# monster_dac.net
KiCad netlist of a schematic drawn in EAGLE
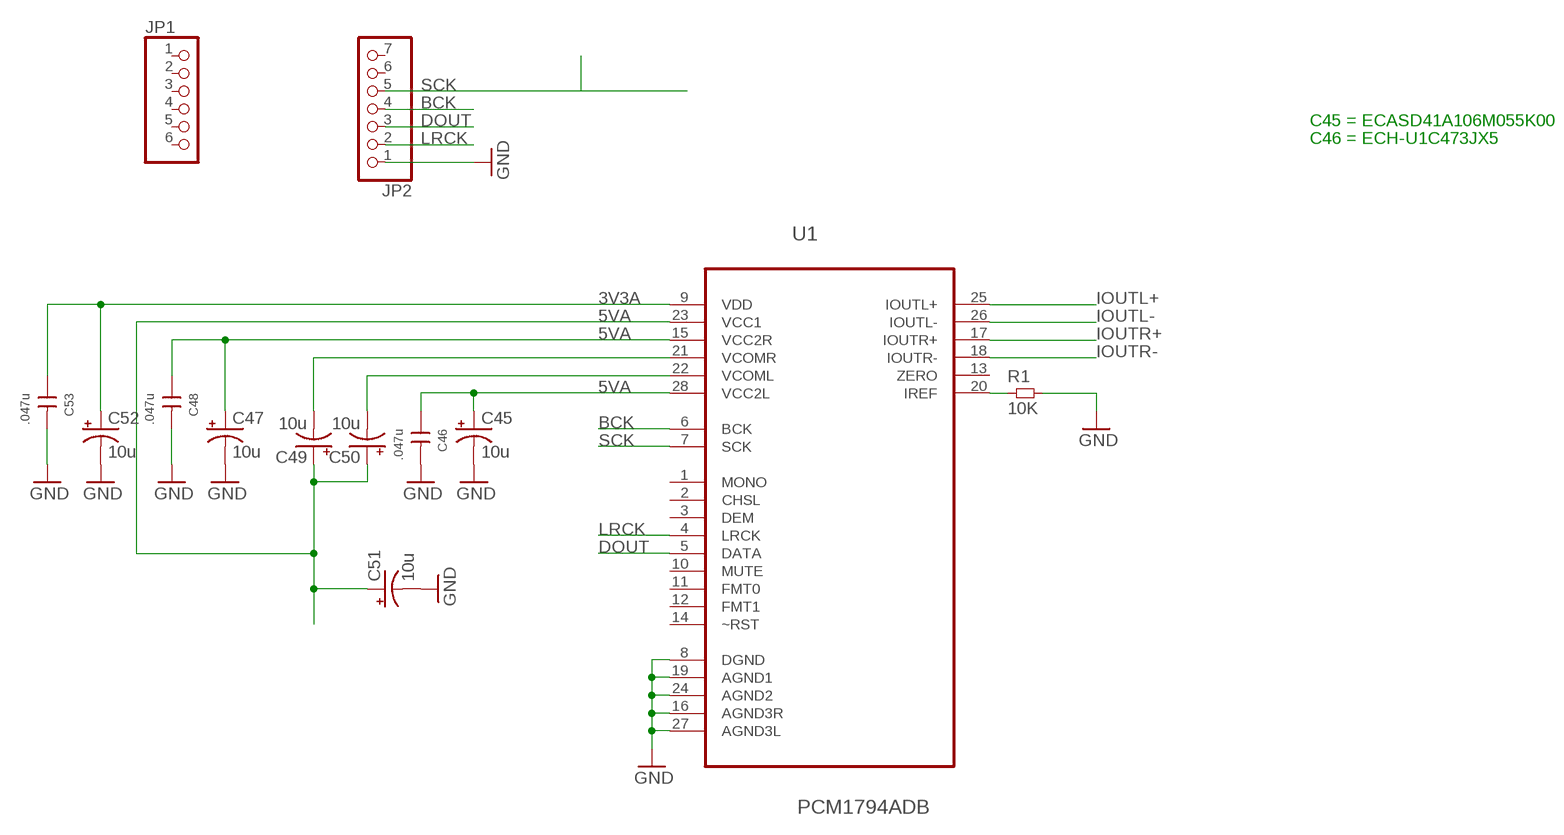
[diagram p0: schematic, sheet 1]
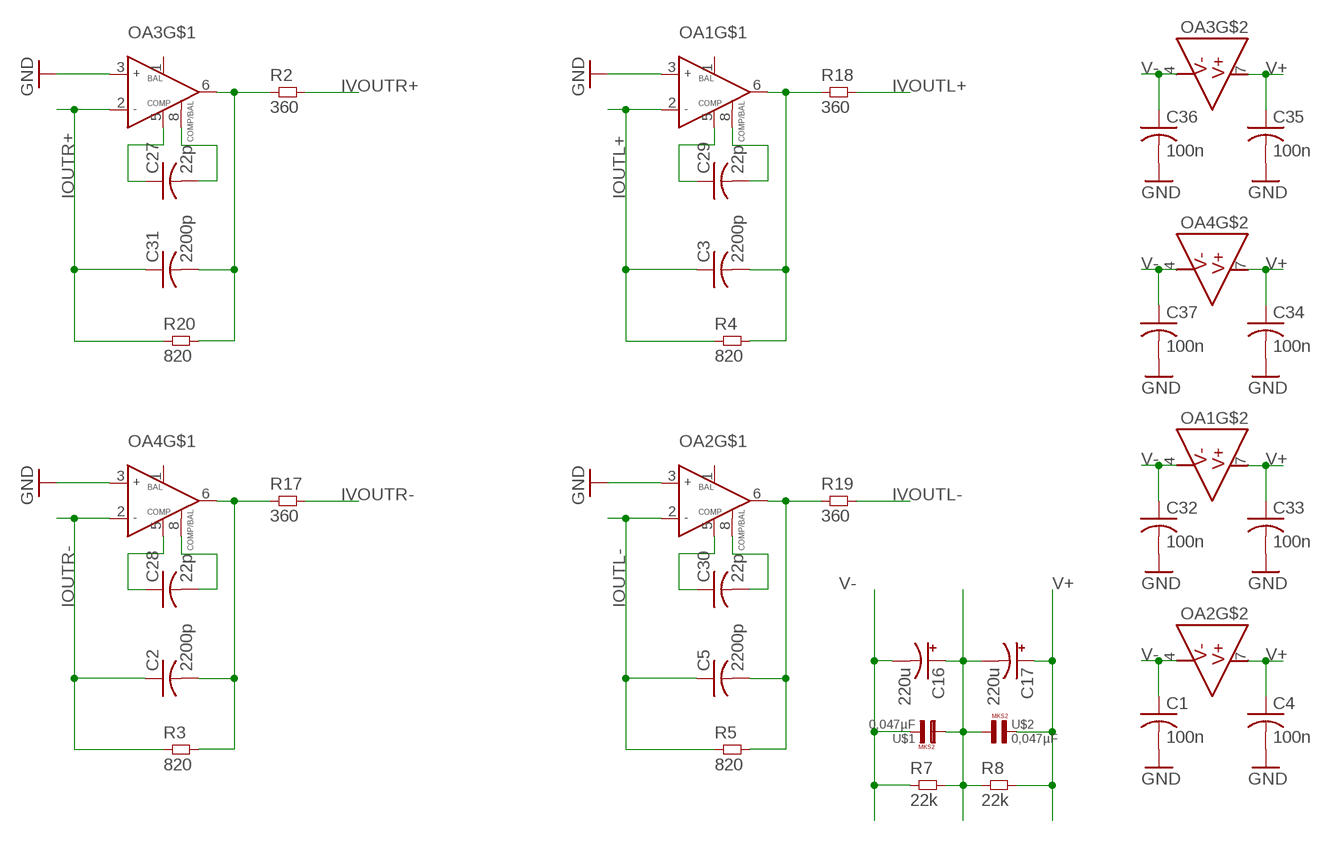
[diagram p1: schematic, sheet 2]
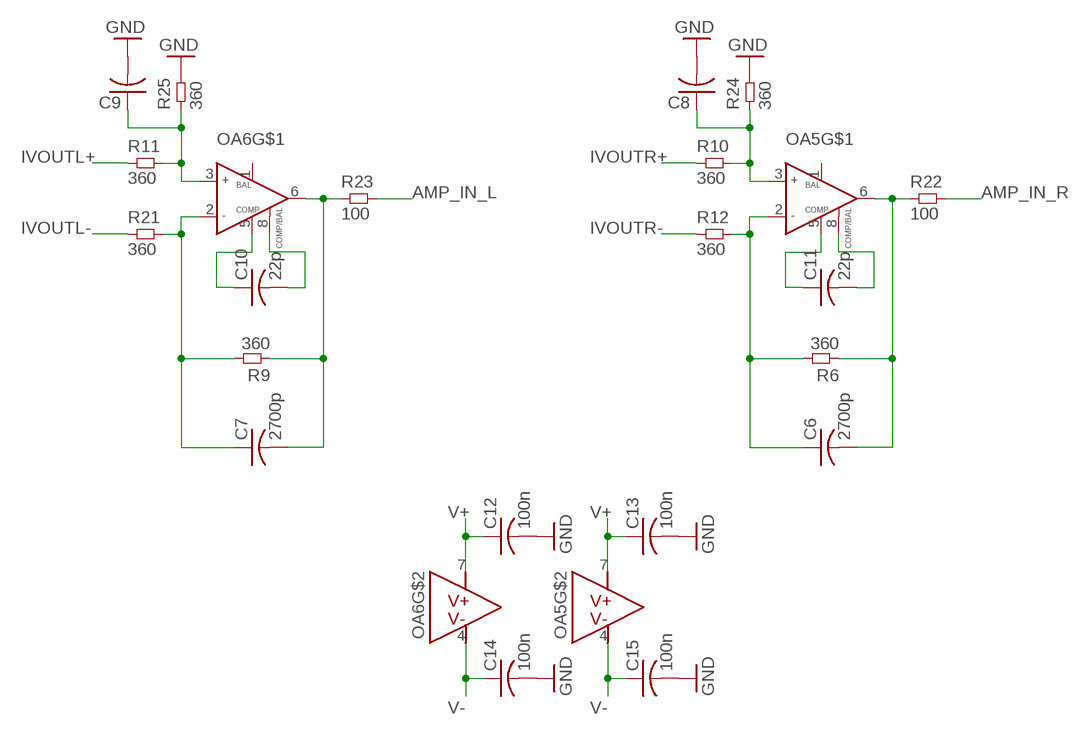
[diagram p2: schematic, sheet 3]

(export (version "E")
  (design (tool "Eeschema 10.0.6"))
  (components
    (comp (ref "C1")
      (value "100n")
      (footprint "eagle-import:C0603")
      (libsource (lib "eagle-import") (part "C-USC0603"))
    )
    (comp (ref "C2")
      (value "2200p")
      (footprint "eagle-import:C0603")
      (libsource (lib "eagle-import") (part "C-USC0603"))
    )
    (comp (ref "C3")
      (value "2200p")
      (footprint "eagle-import:C0603")
      (libsource (lib "eagle-import") (part "C-USC0603"))
    )
    (comp (ref "C4")
      (value "100n")
      (footprint "eagle-import:C0603")
      (libsource (lib "eagle-import") (part "C-USC0603"))
    )
    (comp (ref "C5")
      (value "2200p")
      (footprint "eagle-import:C0603")
      (libsource (lib "eagle-import") (part "C-USC0603"))
    )
    (comp (ref "C16")
      (value "220u")
      (footprint "eagle-import:E2,5-6")
      (libsource (lib "eagle-import") (part "CPOL-USE2.5-6"))
    )
    (comp (ref "C17")
      (value "220u")
      (footprint "eagle-import:E2,5-6")
      (libsource (lib "eagle-import") (part "CPOL-USE2.5-6"))
    )
    (comp (ref "C27")
      (value "22p")
      (footprint "eagle-import:C0603")
      (libsource (lib "eagle-import") (part "C-USC0603"))
    )
    (comp (ref "C28")
      (value "22p")
      (footprint "eagle-import:C0603")
      (libsource (lib "eagle-import") (part "C-USC0603"))
    )
    (comp (ref "C29")
      (value "22p")
      (footprint "eagle-import:C0603")
      (libsource (lib "eagle-import") (part "C-USC0603"))
    )
    (comp (ref "C30")
      (value "22p")
      (footprint "eagle-import:C0603")
      (libsource (lib "eagle-import") (part "C-USC0603"))
    )
    (comp (ref "C31")
      (value "2200p")
      (footprint "eagle-import:C0603")
      (libsource (lib "eagle-import") (part "C-USC0603"))
    )
    (comp (ref "C32")
      (value "100n")
      (footprint "eagle-import:C0603")
      (libsource (lib "eagle-import") (part "C-USC0603"))
    )
    (comp (ref "C33")
      (value "100n")
      (footprint "eagle-import:C0603")
      (libsource (lib "eagle-import") (part "C-USC0603"))
    )
    (comp (ref "C34")
      (value "100n")
      (footprint "eagle-import:C0603")
      (libsource (lib "eagle-import") (part "C-USC0603"))
    )
    (comp (ref "C35")
      (value "100n")
      (footprint "eagle-import:C0603")
      (libsource (lib "eagle-import") (part "C-USC0603"))
    )
    (comp (ref "C36")
      (value "100n")
      (footprint "eagle-import:C0603")
      (libsource (lib "eagle-import") (part "C-USC0603"))
    )
    (comp (ref "C37")
      (value "100n")
      (footprint "eagle-import:C0603")
      (libsource (lib "eagle-import") (part "C-USC0603"))
    )
    (comp (ref "OA1")
      (value "NE5534ADSOIC8")
      (footprint "eagle-import:SOIC-8")
      (libsource (lib "eagle-import") (part "NE5534SOIC8AD"))
    )
    (comp (ref "OA2")
      (value "NE5534ADSOIC8")
      (footprint "eagle-import:SOIC-8")
      (libsource (lib "eagle-import") (part "NE5534SOIC8AD"))
    )
    (comp (ref "OA3")
      (value "NE5534ADSOIC8")
      (footprint "eagle-import:SOIC-8")
      (libsource (lib "eagle-import") (part "NE5534SOIC8AD"))
    )
    (comp (ref "OA4")
      (value "NE5534ADSOIC8")
      (footprint "eagle-import:SOIC-8")
      (libsource (lib "eagle-import") (part "NE5534SOIC8AD"))
    )
    (comp (ref "R2")
      (value "360")
      (footprint "eagle-import:0603L3")
      (libsource (lib "eagle-import") (part "RES0603L3"))
    )
    (comp (ref "R3")
      (value "820")
      (footprint "eagle-import:0603L3")
      (libsource (lib "eagle-import") (part "RES0603L3"))
    )
    (comp (ref "R4")
      (value "820")
      (footprint "eagle-import:0603L3")
      (libsource (lib "eagle-import") (part "RES0603L3"))
    )
    (comp (ref "R5")
      (value "820")
      (footprint "eagle-import:0603L3")
      (libsource (lib "eagle-import") (part "RES0603L3"))
    )
    (comp (ref "R7")
      (value "22k")
      (footprint "eagle-import:0603L3")
      (libsource (lib "eagle-import") (part "RES0603L3"))
    )
    (comp (ref "R8")
      (value "22k")
      (footprint "eagle-import:0603L3")
      (libsource (lib "eagle-import") (part "RES0603L3"))
    )
    (comp (ref "R17")
      (value "360")
      (footprint "eagle-import:0603L3")
      (libsource (lib "eagle-import") (part "RES0603L3"))
    )
    (comp (ref "R18")
      (value "360")
      (footprint "eagle-import:0603L3")
      (libsource (lib "eagle-import") (part "RES0603L3"))
    )
    (comp (ref "R19")
      (value "360")
      (footprint "eagle-import:0603L3")
      (libsource (lib "eagle-import") (part "RES0603L3"))
    )
    (comp (ref "R20")
      (value "820")
      (footprint "eagle-import:0603L3")
      (libsource (lib "eagle-import") (part "RES0603L3"))
    )
    (comp (ref "U$1")
      (value "0,047µF")
      (footprint "eagle-import:R5B2K5")
      (libsource (lib "eagle-import") (part "0,047µF"))
    )
    (comp (ref "U$2")
      (value "0,047µF")
      (footprint "eagle-import:R5B2K5")
      (libsource (lib "eagle-import") (part "0,047µF"))
    )
    (comp (ref "C6")
      (value "2700p")
      (footprint "eagle-import:C0603")
      (libsource (lib "eagle-import") (part "C-USC0603"))
    )
    (comp (ref "C7")
      (value "2700p")
      (footprint "eagle-import:C0603")
      (libsource (lib "eagle-import") (part "C-USC0603"))
    )
    (comp (ref "C8")
      (value "C-USC0603")
      (footprint "eagle-import:C0603")
      (libsource (lib "eagle-import") (part "C-USC0603"))
    )
    (comp (ref "C9")
      (value "C-USC0603")
      (footprint "eagle-import:C0603")
      (libsource (lib "eagle-import") (part "C-USC0603"))
    )
    (comp (ref "C10")
      (value "22p")
      (footprint "eagle-import:C0603")
      (libsource (lib "eagle-import") (part "C-USC0603"))
    )
    (comp (ref "C11")
      (value "22p")
      (footprint "eagle-import:C0603")
      (libsource (lib "eagle-import") (part "C-USC0603"))
    )
    (comp (ref "C12")
      (value "100n")
      (footprint "eagle-import:C0603")
      (libsource (lib "eagle-import") (part "C-USC0603"))
    )
    (comp (ref "C13")
      (value "100n")
      (footprint "eagle-import:C0603")
      (libsource (lib "eagle-import") (part "C-USC0603"))
    )
    (comp (ref "C14")
      (value "100n")
      (footprint "eagle-import:C0603")
      (libsource (lib "eagle-import") (part "C-USC0603"))
    )
    (comp (ref "C15")
      (value "100n")
      (footprint "eagle-import:C0603")
      (libsource (lib "eagle-import") (part "C-USC0603"))
    )
    (comp (ref "OA5")
      (value "NE5534ADSOIC8")
      (footprint "eagle-import:SOIC-8")
      (libsource (lib "eagle-import") (part "NE5534SOIC8AD"))
    )
    (comp (ref "OA6")
      (value "NE5534ADSOIC8")
      (footprint "eagle-import:SOIC-8")
      (libsource (lib "eagle-import") (part "NE5534SOIC8AD"))
    )
    (comp (ref "R6")
      (value "360")
      (footprint "eagle-import:0603L3")
      (libsource (lib "eagle-import") (part "RES0603L3"))
    )
    (comp (ref "R9")
      (value "360")
      (footprint "eagle-import:0603L3")
      (libsource (lib "eagle-import") (part "RES0603L3"))
    )
    (comp (ref "R10")
      (value "360")
      (footprint "eagle-import:0603L3")
      (libsource (lib "eagle-import") (part "RES0603L3"))
    )
    (comp (ref "R11")
      (value "360")
      (footprint "eagle-import:0603L3")
      (libsource (lib "eagle-import") (part "RES0603L3"))
    )
    (comp (ref "R12")
      (value "360")
      (footprint "eagle-import:0603L3")
      (libsource (lib "eagle-import") (part "RES0603L3"))
    )
    (comp (ref "R21")
      (value "360")
      (footprint "eagle-import:0603L3")
      (libsource (lib "eagle-import") (part "RES0603L3"))
    )
    (comp (ref "R22")
      (value "100")
      (footprint "eagle-import:0603L3")
      (libsource (lib "eagle-import") (part "RES0603L3"))
    )
    (comp (ref "R23")
      (value "100")
      (footprint "eagle-import:0603L3")
      (libsource (lib "eagle-import") (part "RES0603L3"))
    )
    (comp (ref "R24")
      (value "360")
      (footprint "eagle-import:0603L3")
      (libsource (lib "eagle-import") (part "RES0603L3"))
    )
    (comp (ref "R25")
      (value "360")
      (footprint "eagle-import:0603L3")
      (libsource (lib "eagle-import") (part "RES0603L3"))
    )
    (comp (ref "C45")
      (value "10u")
      (footprint "eagle-import:E2-5")
      (libsource (lib "eagle-import") (part "CPOL-USE2-5"))
    )
    (comp (ref "C46")
      (value ".047u")
      (footprint "eagle-import:2,5X6,5RM5,0")
      (libsource (lib "eagle-import") (part "47NF63VMKS2"))
    )
    (comp (ref "C47")
      (value "10u")
      (footprint "eagle-import:E2-5")
      (libsource (lib "eagle-import") (part "CPOL-USE2-5"))
    )
    (comp (ref "C48")
      (value ".047u")
      (footprint "eagle-import:2,5X6,5RM5,0")
      (libsource (lib "eagle-import") (part "47NF63VMKS2"))
    )
    (comp (ref "C49")
      (value "10u")
      (footprint "eagle-import:E2-5")
      (libsource (lib "eagle-import") (part "CPOL-USE2-5"))
    )
    (comp (ref "C50")
      (value "10u")
      (footprint "eagle-import:E2-5")
      (libsource (lib "eagle-import") (part "CPOL-USE2-5"))
    )
    (comp (ref "C51")
      (value "10u")
      (footprint "eagle-import:E2-5")
      (libsource (lib "eagle-import") (part "CPOL-USE2-5"))
    )
    (comp (ref "C52")
      (value "10u")
      (footprint "eagle-import:E2-5")
      (libsource (lib "eagle-import") (part "CPOL-USE2-5"))
    )
    (comp (ref "C53")
      (value ".047u")
      (footprint "eagle-import:2,5X6,5RM5,0")
      (libsource (lib "eagle-import") (part "47NF63VMKS2"))
    )
    (comp (ref "JP1")
      (value "PINHD-1X6")
      (footprint "eagle-import:1X06")
      (libsource (lib "eagle-import") (part "PINHD-1X6"))
    )
    (comp (ref "JP2")
      (value "PINHD-1X7")
      (footprint "eagle-import:1X07")
      (libsource (lib "eagle-import") (part "PINHD-1X7"))
    )
    (comp (ref "R1")
      (value "10K")
      (footprint "eagle-import:0603L3")
      (libsource (lib "eagle-import") (part "RES0603L3"))
    )
    (comp (ref "U1")
      (value "PCM1794ADB")
      (footprint "eagle-import:SOP65P780X200-28N")
      (libsource (lib "eagle-import") (part "PCM1794ADB"))
    )
  )
  (nets
    (net (code "1") (name "3V3A") (class "Default")
      (node (ref "C52") (pin "+") (pinfunction "+_+") (pintype "passive"))
      (node (ref "C53") (pin "1") (pinfunction "1_1") (pintype "passive"))
      (node (ref "U1") (pin "9") (pinfunction "VDD_9") (pintype "power_in"))
    )
    (net (code "2") (name "5VA") (class "Default")
      (node (ref "C45") (pin "+") (pinfunction "+_+") (pintype "passive"))
      (node (ref "C46") (pin "1") (pinfunction "1_1") (pintype "passive"))
      (node (ref "C47") (pin "+") (pinfunction "+_+") (pintype "passive"))
      (node (ref "C48") (pin "1") (pinfunction "1_1") (pintype "passive"))
      (node (ref "C49") (pin "+") (pinfunction "+_+") (pintype "passive"))
      (node (ref "C50") (pin "+") (pinfunction "+_+") (pintype "passive"))
      (node (ref "C51") (pin "+") (pinfunction "+_+") (pintype "passive"))
      (node (ref "U1") (pin "15") (pinfunction "VCC2R_15") (pintype "power_in"))
      (node (ref "U1") (pin "23") (pinfunction "VCC1_23") (pintype "power_in"))
      (node (ref "U1") (pin "28") (pinfunction "VCC2L_28") (pintype "power_in"))
    )
    (net (code "3") (name "AMP_IN_L") (class "Default")
      (node (ref "R23") (pin "P$2") (pinfunction "2_P$2") (pintype "bidirectional"))
    )
    (net (code "4") (name "AMP_IN_R") (class "Default")
      (node (ref "R22") (pin "P$2") (pinfunction "2_P$2") (pintype "bidirectional"))
    )
    (net (code "5") (name "BCK") (class "Default")
      (node (ref "JP2") (pin "4") (pinfunction "4_4") (pintype "passive"))
      (node (ref "U1") (pin "6") (pinfunction "BCK_6") (pintype "input"))
    )
    (net (code "6") (name "DOUT") (class "Default")
      (node (ref "JP2") (pin "3") (pinfunction "3_3") (pintype "passive"))
      (node (ref "U1") (pin "5") (pinfunction "DATA_5") (pintype "input"))
    )
    (net (code "7") (name "GND") (class "Default")
      (node (ref "C1") (pin "2") (pinfunction "2_2") (pintype "passive"))
      (node (ref "C12") (pin "2") (pinfunction "2_2") (pintype "passive"))
      (node (ref "C13") (pin "2") (pinfunction "2_2") (pintype "passive"))
      (node (ref "C14") (pin "2") (pinfunction "2_2") (pintype "passive"))
      (node (ref "C15") (pin "2") (pinfunction "2_2") (pintype "passive"))
      (node (ref "C16") (pin "+") (pinfunction "+_+") (pintype "passive"))
      (node (ref "C17") (pin "-") (pinfunction "-_-") (pintype "passive"))
      (node (ref "C32") (pin "2") (pinfunction "2_2") (pintype "passive"))
      (node (ref "C33") (pin "2") (pinfunction "2_2") (pintype "passive"))
      (node (ref "C34") (pin "2") (pinfunction "2_2") (pintype "passive"))
      (node (ref "C35") (pin "2") (pinfunction "2_2") (pintype "passive"))
      (node (ref "C36") (pin "2") (pinfunction "2_2") (pintype "passive"))
      (node (ref "C37") (pin "2") (pinfunction "2_2") (pintype "passive"))
      (node (ref "C4") (pin "2") (pinfunction "2_2") (pintype "passive"))
      (node (ref "C45") (pin "-") (pinfunction "-_-") (pintype "passive"))
      (node (ref "C46") (pin "2") (pinfunction "2_2") (pintype "passive"))
      (node (ref "C47") (pin "-") (pinfunction "-_-") (pintype "passive"))
      (node (ref "C48") (pin "2") (pinfunction "2_2") (pintype "passive"))
      (node (ref "C51") (pin "-") (pinfunction "-_-") (pintype "passive"))
      (node (ref "C52") (pin "-") (pinfunction "-_-") (pintype "passive"))
      (node (ref "C53") (pin "2") (pinfunction "2_2") (pintype "passive"))
      (node (ref "C8") (pin "2") (pinfunction "2_2") (pintype "passive"))
      (node (ref "C9") (pin "2") (pinfunction "2_2") (pintype "passive"))
      (node (ref "JP2") (pin "1") (pinfunction "1_1") (pintype "passive"))
      (node (ref "OA1") (pin "3") (pinfunction "IN+_3") (pintype "bidirectional"))
      (node (ref "OA2") (pin "3") (pinfunction "IN+_3") (pintype "bidirectional"))
      (node (ref "OA3") (pin "3") (pinfunction "IN+_3") (pintype "bidirectional"))
      (node (ref "OA4") (pin "3") (pinfunction "IN+_3") (pintype "bidirectional"))
      (node (ref "R1") (pin "P$2") (pinfunction "2_P$2") (pintype "bidirectional"))
      (node (ref "R24") (pin "P$2") (pinfunction "2_P$2") (pintype "bidirectional"))
      (node (ref "R25") (pin "P$2") (pinfunction "2_P$2") (pintype "bidirectional"))
      (node (ref "R7") (pin "P$2") (pinfunction "2_P$2") (pintype "bidirectional"))
      (node (ref "R8") (pin "P$1") (pinfunction "1_P$1") (pintype "bidirectional"))
      (node (ref "U$1") (pin "1") (pinfunction "1_1") (pintype "passive"))
      (node (ref "U$2") (pin "1") (pinfunction "1_1") (pintype "passive"))
      (node (ref "U1") (pin "16") (pinfunction "AGND3R_16") (pintype "passive"))
      (node (ref "U1") (pin "19") (pinfunction "AGND1_19") (pintype "passive"))
      (node (ref "U1") (pin "24") (pinfunction "AGND2_24") (pintype "passive"))
      (node (ref "U1") (pin "27") (pinfunction "AGND3L_27") (pintype "passive"))
      (node (ref "U1") (pin "8") (pinfunction "DGND_8") (pintype "passive"))
    )
    (net (code "8") (name "IOUTL+") (class "Default")
      (node (ref "C3") (pin "1") (pinfunction "1_1") (pintype "passive"))
      (node (ref "OA1") (pin "2") (pinfunction "IN-_2") (pintype "bidirectional"))
      (node (ref "R4") (pin "P$1") (pinfunction "1_P$1") (pintype "bidirectional"))
      (node (ref "U1") (pin "25") (pinfunction "IOUTL+_25") (pintype "output"))
    )
    (net (code "9") (name "IOUTL-") (class "Default")
      (node (ref "C5") (pin "1") (pinfunction "1_1") (pintype "passive"))
      (node (ref "OA2") (pin "2") (pinfunction "IN-_2") (pintype "bidirectional"))
      (node (ref "R5") (pin "P$1") (pinfunction "1_P$1") (pintype "bidirectional"))
      (node (ref "U1") (pin "26") (pinfunction "IOUTL-_26") (pintype "output"))
    )
    (net (code "10") (name "IOUTR+") (class "Default")
      (node (ref "C31") (pin "1") (pinfunction "1_1") (pintype "passive"))
      (node (ref "OA3") (pin "2") (pinfunction "IN-_2") (pintype "bidirectional"))
      (node (ref "R20") (pin "P$1") (pinfunction "1_P$1") (pintype "bidirectional"))
      (node (ref "U1") (pin "17") (pinfunction "IOUTR+_17") (pintype "output"))
    )
    (net (code "11") (name "IOUTR-") (class "Default")
      (node (ref "C2") (pin "1") (pinfunction "1_1") (pintype "passive"))
      (node (ref "OA4") (pin "2") (pinfunction "IN-_2") (pintype "bidirectional"))
      (node (ref "R3") (pin "P$1") (pinfunction "1_P$1") (pintype "bidirectional"))
      (node (ref "U1") (pin "18") (pinfunction "IOUTR-_18") (pintype "output"))
    )
    (net (code "12") (name "IVOUTL+") (class "Default")
      (node (ref "R11") (pin "P$1") (pinfunction "1_P$1") (pintype "bidirectional"))
      (node (ref "R18") (pin "P$2") (pinfunction "2_P$2") (pintype "bidirectional"))
    )
    (net (code "13") (name "IVOUTL-") (class "Default")
      (node (ref "R19") (pin "P$2") (pinfunction "2_P$2") (pintype "bidirectional"))
      (node (ref "R21") (pin "P$1") (pinfunction "1_P$1") (pintype "bidirectional"))
    )
    (net (code "14") (name "IVOUTR+") (class "Default")
      (node (ref "R10") (pin "P$1") (pinfunction "1_P$1") (pintype "bidirectional"))
      (node (ref "R2") (pin "P$2") (pinfunction "2_P$2") (pintype "bidirectional"))
    )
    (net (code "15") (name "IVOUTR-") (class "Default")
      (node (ref "R12") (pin "P$1") (pinfunction "1_P$1") (pintype "bidirectional"))
      (node (ref "R17") (pin "P$2") (pinfunction "2_P$2") (pintype "bidirectional"))
    )
    (net (code "16") (name "LRCK") (class "Default")
      (node (ref "JP2") (pin "2") (pinfunction "2_2") (pintype "passive"))
      (node (ref "U1") (pin "4") (pinfunction "LRCK_4") (pintype "input"))
    )
    (net (code "17") (name "Net-(OA1A-COMP)") (class "Default")
      (node (ref "C29") (pin "1") (pinfunction "1_1") (pintype "passive"))
      (node (ref "OA1") (pin "5") (pinfunction "COMP_5") (pintype "bidirectional"))
    )
    (net (code "18") (name "Net-(OA1A-COMP{slash}BAL)") (class "Default")
      (node (ref "C29") (pin "2") (pinfunction "2_2") (pintype "passive"))
      (node (ref "OA1") (pin "8") (pinfunction "COMP/BAL_8") (pintype "bidirectional"))
    )
    (net (code "19") (name "Net-(OA1A-OUT)") (class "Default")
      (node (ref "C3") (pin "2") (pinfunction "2_2") (pintype "passive"))
      (node (ref "OA1") (pin "6") (pinfunction "OUT_6") (pintype "bidirectional"))
      (node (ref "R18") (pin "P$1") (pinfunction "1_P$1") (pintype "bidirectional"))
      (node (ref "R4") (pin "P$2") (pinfunction "2_P$2") (pintype "bidirectional"))
    )
    (net (code "20") (name "Net-(OA2A-COMP)") (class "Default")
      (node (ref "C30") (pin "1") (pinfunction "1_1") (pintype "passive"))
      (node (ref "OA2") (pin "5") (pinfunction "COMP_5") (pintype "bidirectional"))
    )
    (net (code "21") (name "Net-(OA2A-COMP{slash}BAL)") (class "Default")
      (node (ref "C30") (pin "2") (pinfunction "2_2") (pintype "passive"))
      (node (ref "OA2") (pin "8") (pinfunction "COMP/BAL_8") (pintype "bidirectional"))
    )
    (net (code "22") (name "Net-(OA2A-OUT)") (class "Default")
      (node (ref "C5") (pin "2") (pinfunction "2_2") (pintype "passive"))
      (node (ref "OA2") (pin "6") (pinfunction "OUT_6") (pintype "bidirectional"))
      (node (ref "R19") (pin "P$1") (pinfunction "1_P$1") (pintype "bidirectional"))
      (node (ref "R5") (pin "P$2") (pinfunction "2_P$2") (pintype "bidirectional"))
    )
    (net (code "23") (name "Net-(OA3A-COMP)") (class "Default")
      (node (ref "C27") (pin "1") (pinfunction "1_1") (pintype "passive"))
      (node (ref "OA3") (pin "5") (pinfunction "COMP_5") (pintype "bidirectional"))
    )
    (net (code "24") (name "Net-(OA3A-COMP{slash}BAL)") (class "Default")
      (node (ref "C27") (pin "2") (pinfunction "2_2") (pintype "passive"))
      (node (ref "OA3") (pin "8") (pinfunction "COMP/BAL_8") (pintype "bidirectional"))
    )
    (net (code "25") (name "Net-(OA3A-OUT)") (class "Default")
      (node (ref "C31") (pin "2") (pinfunction "2_2") (pintype "passive"))
      (node (ref "OA3") (pin "6") (pinfunction "OUT_6") (pintype "bidirectional"))
      (node (ref "R2") (pin "P$1") (pinfunction "1_P$1") (pintype "bidirectional"))
      (node (ref "R20") (pin "P$2") (pinfunction "2_P$2") (pintype "bidirectional"))
    )
    (net (code "26") (name "Net-(OA4A-COMP)") (class "Default")
      (node (ref "C28") (pin "1") (pinfunction "1_1") (pintype "passive"))
      (node (ref "OA4") (pin "5") (pinfunction "COMP_5") (pintype "bidirectional"))
    )
    (net (code "27") (name "Net-(OA4A-COMP{slash}BAL)") (class "Default")
      (node (ref "C28") (pin "2") (pinfunction "2_2") (pintype "passive"))
      (node (ref "OA4") (pin "8") (pinfunction "COMP/BAL_8") (pintype "bidirectional"))
    )
    (net (code "28") (name "Net-(OA4A-OUT)") (class "Default")
      (node (ref "C2") (pin "2") (pinfunction "2_2") (pintype "passive"))
      (node (ref "OA4") (pin "6") (pinfunction "OUT_6") (pintype "bidirectional"))
      (node (ref "R17") (pin "P$1") (pinfunction "1_P$1") (pintype "bidirectional"))
      (node (ref "R3") (pin "P$2") (pinfunction "2_P$2") (pintype "bidirectional"))
    )
    (net (code "29") (name "Net-(OA5A-COMP)") (class "Default")
      (node (ref "C11") (pin "1") (pinfunction "1_1") (pintype "passive"))
      (node (ref "OA5") (pin "5") (pinfunction "COMP_5") (pintype "bidirectional"))
    )
    (net (code "30") (name "Net-(OA5A-COMP{slash}BAL)") (class "Default")
      (node (ref "C11") (pin "2") (pinfunction "2_2") (pintype "passive"))
      (node (ref "OA5") (pin "8") (pinfunction "COMP/BAL_8") (pintype "bidirectional"))
    )
    (net (code "31") (name "Net-(OA5A-IN+)") (class "Default")
      (node (ref "C8") (pin "1") (pinfunction "1_1") (pintype "passive"))
      (node (ref "OA5") (pin "3") (pinfunction "IN+_3") (pintype "bidirectional"))
      (node (ref "R10") (pin "P$2") (pinfunction "2_P$2") (pintype "bidirectional"))
      (node (ref "R24") (pin "P$1") (pinfunction "1_P$1") (pintype "bidirectional"))
    )
    (net (code "32") (name "Net-(OA5A-IN-)") (class "Default")
      (node (ref "C6") (pin "1") (pinfunction "1_1") (pintype "passive"))
      (node (ref "OA5") (pin "2") (pinfunction "IN-_2") (pintype "bidirectional"))
      (node (ref "R12") (pin "P$2") (pinfunction "2_P$2") (pintype "bidirectional"))
      (node (ref "R6") (pin "P$2") (pinfunction "2_P$2") (pintype "bidirectional"))
    )
    (net (code "33") (name "Net-(OA5A-OUT)") (class "Default")
      (node (ref "C6") (pin "2") (pinfunction "2_2") (pintype "passive"))
      (node (ref "OA5") (pin "6") (pinfunction "OUT_6") (pintype "bidirectional"))
      (node (ref "R22") (pin "P$1") (pinfunction "1_P$1") (pintype "bidirectional"))
      (node (ref "R6") (pin "P$1") (pinfunction "1_P$1") (pintype "bidirectional"))
    )
    (net (code "34") (name "Net-(OA6A-COMP)") (class "Default")
      (node (ref "C10") (pin "1") (pinfunction "1_1") (pintype "passive"))
      (node (ref "OA6") (pin "5") (pinfunction "COMP_5") (pintype "bidirectional"))
    )
    (net (code "35") (name "Net-(OA6A-COMP{slash}BAL)") (class "Default")
      (node (ref "C10") (pin "2") (pinfunction "2_2") (pintype "passive"))
      (node (ref "OA6") (pin "8") (pinfunction "COMP/BAL_8") (pintype "bidirectional"))
    )
    (net (code "36") (name "Net-(OA6A-IN+)") (class "Default")
      (node (ref "C9") (pin "1") (pinfunction "1_1") (pintype "passive"))
      (node (ref "OA6") (pin "3") (pinfunction "IN+_3") (pintype "bidirectional"))
      (node (ref "R11") (pin "P$2") (pinfunction "2_P$2") (pintype "bidirectional"))
      (node (ref "R25") (pin "P$1") (pinfunction "1_P$1") (pintype "bidirectional"))
    )
    (net (code "37") (name "Net-(OA6A-IN-)") (class "Default")
      (node (ref "C7") (pin "1") (pinfunction "1_1") (pintype "passive"))
      (node (ref "OA6") (pin "2") (pinfunction "IN-_2") (pintype "bidirectional"))
      (node (ref "R21") (pin "P$2") (pinfunction "2_P$2") (pintype "bidirectional"))
      (node (ref "R9") (pin "P$2") (pinfunction "2_P$2") (pintype "bidirectional"))
    )
    (net (code "38") (name "Net-(OA6A-OUT)") (class "Default")
      (node (ref "C7") (pin "2") (pinfunction "2_2") (pintype "passive"))
      (node (ref "OA6") (pin "6") (pinfunction "OUT_6") (pintype "bidirectional"))
      (node (ref "R23") (pin "P$1") (pinfunction "1_P$1") (pintype "bidirectional"))
      (node (ref "R9") (pin "P$1") (pinfunction "1_P$1") (pintype "bidirectional"))
    )
    (net (code "39") (name "Net-(R1-1)") (class "Default")
      (node (ref "R1") (pin "P$1") (pinfunction "1_P$1") (pintype "bidirectional"))
      (node (ref "U1") (pin "20") (pinfunction "IREF_20") (pintype "output"))
    )
    (net (code "40") (name "Net-(U1-VCOML)") (class "Default")
      (node (ref "C50") (pin "-") (pinfunction "-_-") (pintype "passive"))
      (node (ref "U1") (pin "22") (pinfunction "VCOML_22") (pintype "input"))
    )
    (net (code "41") (name "Net-(U1-VCOMR)") (class "Default")
      (node (ref "C49") (pin "-") (pinfunction "-_-") (pintype "passive"))
      (node (ref "U1") (pin "21") (pinfunction "VCOMR_21") (pintype "input"))
    )
    (net (code "42") (name "SCK") (class "Default")
      (node (ref "JP2") (pin "5") (pinfunction "5_5") (pintype "passive"))
      (node (ref "U1") (pin "7") (pinfunction "SCK_7") (pintype "input"))
    )
    (net (code "43") (name "V+") (class "Default")
      (node (ref "C12") (pin "1") (pinfunction "1_1") (pintype "passive"))
      (node (ref "C13") (pin "1") (pinfunction "1_1") (pintype "passive"))
      (node (ref "C17") (pin "+") (pinfunction "+_+") (pintype "passive"))
      (node (ref "C33") (pin "1") (pinfunction "1_1") (pintype "passive"))
      (node (ref "C34") (pin "1") (pinfunction "1_1") (pintype "passive"))
      (node (ref "C35") (pin "1") (pinfunction "1_1") (pintype "passive"))
      (node (ref "C4") (pin "1") (pinfunction "1_1") (pintype "passive"))
      (node (ref "OA1") (pin "7") (pinfunction "V+_7") (pintype "power_in"))
      (node (ref "OA2") (pin "7") (pinfunction "V+_7") (pintype "power_in"))
      (node (ref "OA3") (pin "7") (pinfunction "V+_7") (pintype "power_in"))
      (node (ref "OA4") (pin "7") (pinfunction "V+_7") (pintype "power_in"))
      (node (ref "OA5") (pin "7") (pinfunction "V+_7") (pintype "power_in"))
      (node (ref "OA6") (pin "7") (pinfunction "V+_7") (pintype "power_in"))
      (node (ref "R8") (pin "P$2") (pinfunction "2_P$2") (pintype "bidirectional"))
      (node (ref "U$2") (pin "2") (pinfunction "2_2") (pintype "passive"))
    )
    (net (code "44") (name "V-") (class "Default")
      (node (ref "C1") (pin "1") (pinfunction "1_1") (pintype "passive"))
      (node (ref "C14") (pin "1") (pinfunction "1_1") (pintype "passive"))
      (node (ref "C15") (pin "1") (pinfunction "1_1") (pintype "passive"))
      (node (ref "C16") (pin "-") (pinfunction "-_-") (pintype "passive"))
      (node (ref "C32") (pin "1") (pinfunction "1_1") (pintype "passive"))
      (node (ref "C36") (pin "1") (pinfunction "1_1") (pintype "passive"))
      (node (ref "C37") (pin "1") (pinfunction "1_1") (pintype "passive"))
      (node (ref "OA1") (pin "4") (pinfunction "V-_4") (pintype "power_in"))
      (node (ref "OA2") (pin "4") (pinfunction "V-_4") (pintype "power_in"))
      (node (ref "OA3") (pin "4") (pinfunction "V-_4") (pintype "power_in"))
      (node (ref "OA4") (pin "4") (pinfunction "V-_4") (pintype "power_in"))
      (node (ref "OA5") (pin "4") (pinfunction "V-_4") (pintype "power_in"))
      (node (ref "OA6") (pin "4") (pinfunction "V-_4") (pintype "power_in"))
      (node (ref "R7") (pin "P$1") (pinfunction "1_P$1") (pintype "bidirectional"))
      (node (ref "U$1") (pin "2") (pinfunction "2_2") (pintype "passive"))
    )
    (net (code "45") (name "unconnected-(JP1-Pad1)") (class "Default")
      (node (ref "JP1") (pin "1") (pinfunction "1_1") (pintype "passive"))
    )
    (net (code "46") (name "unconnected-(JP1-Pad2)") (class "Default")
      (node (ref "JP1") (pin "2") (pinfunction "2_2") (pintype "passive"))
    )
    (net (code "47") (name "unconnected-(JP1-Pad3)") (class "Default")
      (node (ref "JP1") (pin "3") (pinfunction "3_3") (pintype "passive"))
    )
    (net (code "48") (name "unconnected-(JP1-Pad4)") (class "Default")
      (node (ref "JP1") (pin "4") (pinfunction "4_4") (pintype "passive"))
    )
    (net (code "49") (name "unconnected-(JP1-Pad5)") (class "Default")
      (node (ref "JP1") (pin "5") (pinfunction "5_5") (pintype "passive"))
    )
    (net (code "50") (name "unconnected-(JP1-Pad6)") (class "Default")
      (node (ref "JP1") (pin "6") (pinfunction "6_6") (pintype "passive"))
    )
    (net (code "51") (name "unconnected-(JP2-Pad6)") (class "Default")
      (node (ref "JP2") (pin "6") (pinfunction "6_6") (pintype "passive"))
    )
    (net (code "52") (name "unconnected-(JP2-Pad7)") (class "Default")
      (node (ref "JP2") (pin "7") (pinfunction "7_7") (pintype "passive"))
    )
    (net (code "53") (name "unconnected-(OA1A-BAL-Pad1)") (class "Default")
      (node (ref "OA1") (pin "1") (pinfunction "BAL_1") (pintype "bidirectional"))
    )
    (net (code "54") (name "unconnected-(OA2A-BAL-Pad1)") (class "Default")
      (node (ref "OA2") (pin "1") (pinfunction "BAL_1") (pintype "bidirectional"))
    )
    (net (code "55") (name "unconnected-(OA3A-BAL-Pad1)") (class "Default")
      (node (ref "OA3") (pin "1") (pinfunction "BAL_1") (pintype "bidirectional"))
    )
    (net (code "56") (name "unconnected-(OA4A-BAL-Pad1)") (class "Default")
      (node (ref "OA4") (pin "1") (pinfunction "BAL_1") (pintype "bidirectional"))
    )
    (net (code "57") (name "unconnected-(OA5A-BAL-Pad1)") (class "Default")
      (node (ref "OA5") (pin "1") (pinfunction "BAL_1") (pintype "bidirectional"))
    )
    (net (code "58") (name "unconnected-(OA6A-BAL-Pad1)") (class "Default")
      (node (ref "OA6") (pin "1") (pinfunction "BAL_1") (pintype "bidirectional"))
    )
    (net (code "59") (name "unconnected-(U1-CHSL-Pad2)") (class "Default")
      (node (ref "U1") (pin "2") (pinfunction "CHSL_2") (pintype "input"))
    )
    (net (code "60") (name "unconnected-(U1-DEM-Pad3)") (class "Default")
      (node (ref "U1") (pin "3") (pinfunction "DEM_3") (pintype "input"))
    )
    (net (code "61") (name "unconnected-(U1-FMT0-Pad11)") (class "Default")
      (node (ref "U1") (pin "11") (pinfunction "FMT0_11") (pintype "input"))
    )
    (net (code "62") (name "unconnected-(U1-FMT1-Pad12)") (class "Default")
      (node (ref "U1") (pin "12") (pinfunction "FMT1_12") (pintype "input"))
    )
    (net (code "63") (name "unconnected-(U1-MONO-Pad1)") (class "Default")
      (node (ref "U1") (pin "1") (pinfunction "MONO_1") (pintype "input"))
    )
    (net (code "64") (name "unconnected-(U1-MUTE-Pad10)") (class "Default")
      (node (ref "U1") (pin "10") (pinfunction "MUTE_10") (pintype "input"))
    )
    (net (code "65") (name "unconnected-(U1-ZERO-Pad13)") (class "Default")
      (node (ref "U1") (pin "13") (pinfunction "ZERO_13") (pintype "output"))
    )
    (net (code "66") (name "unconnected-(U1-~{RST}-Pad14)") (class "Default")
      (node (ref "U1") (pin "14") (pinfunction "~{RST}_14") (pintype "input"))
    )
  )
)
